# 2in-2out_1_0f_produziert_re.net
KiCad netlist of a schematic drawn in EAGLE
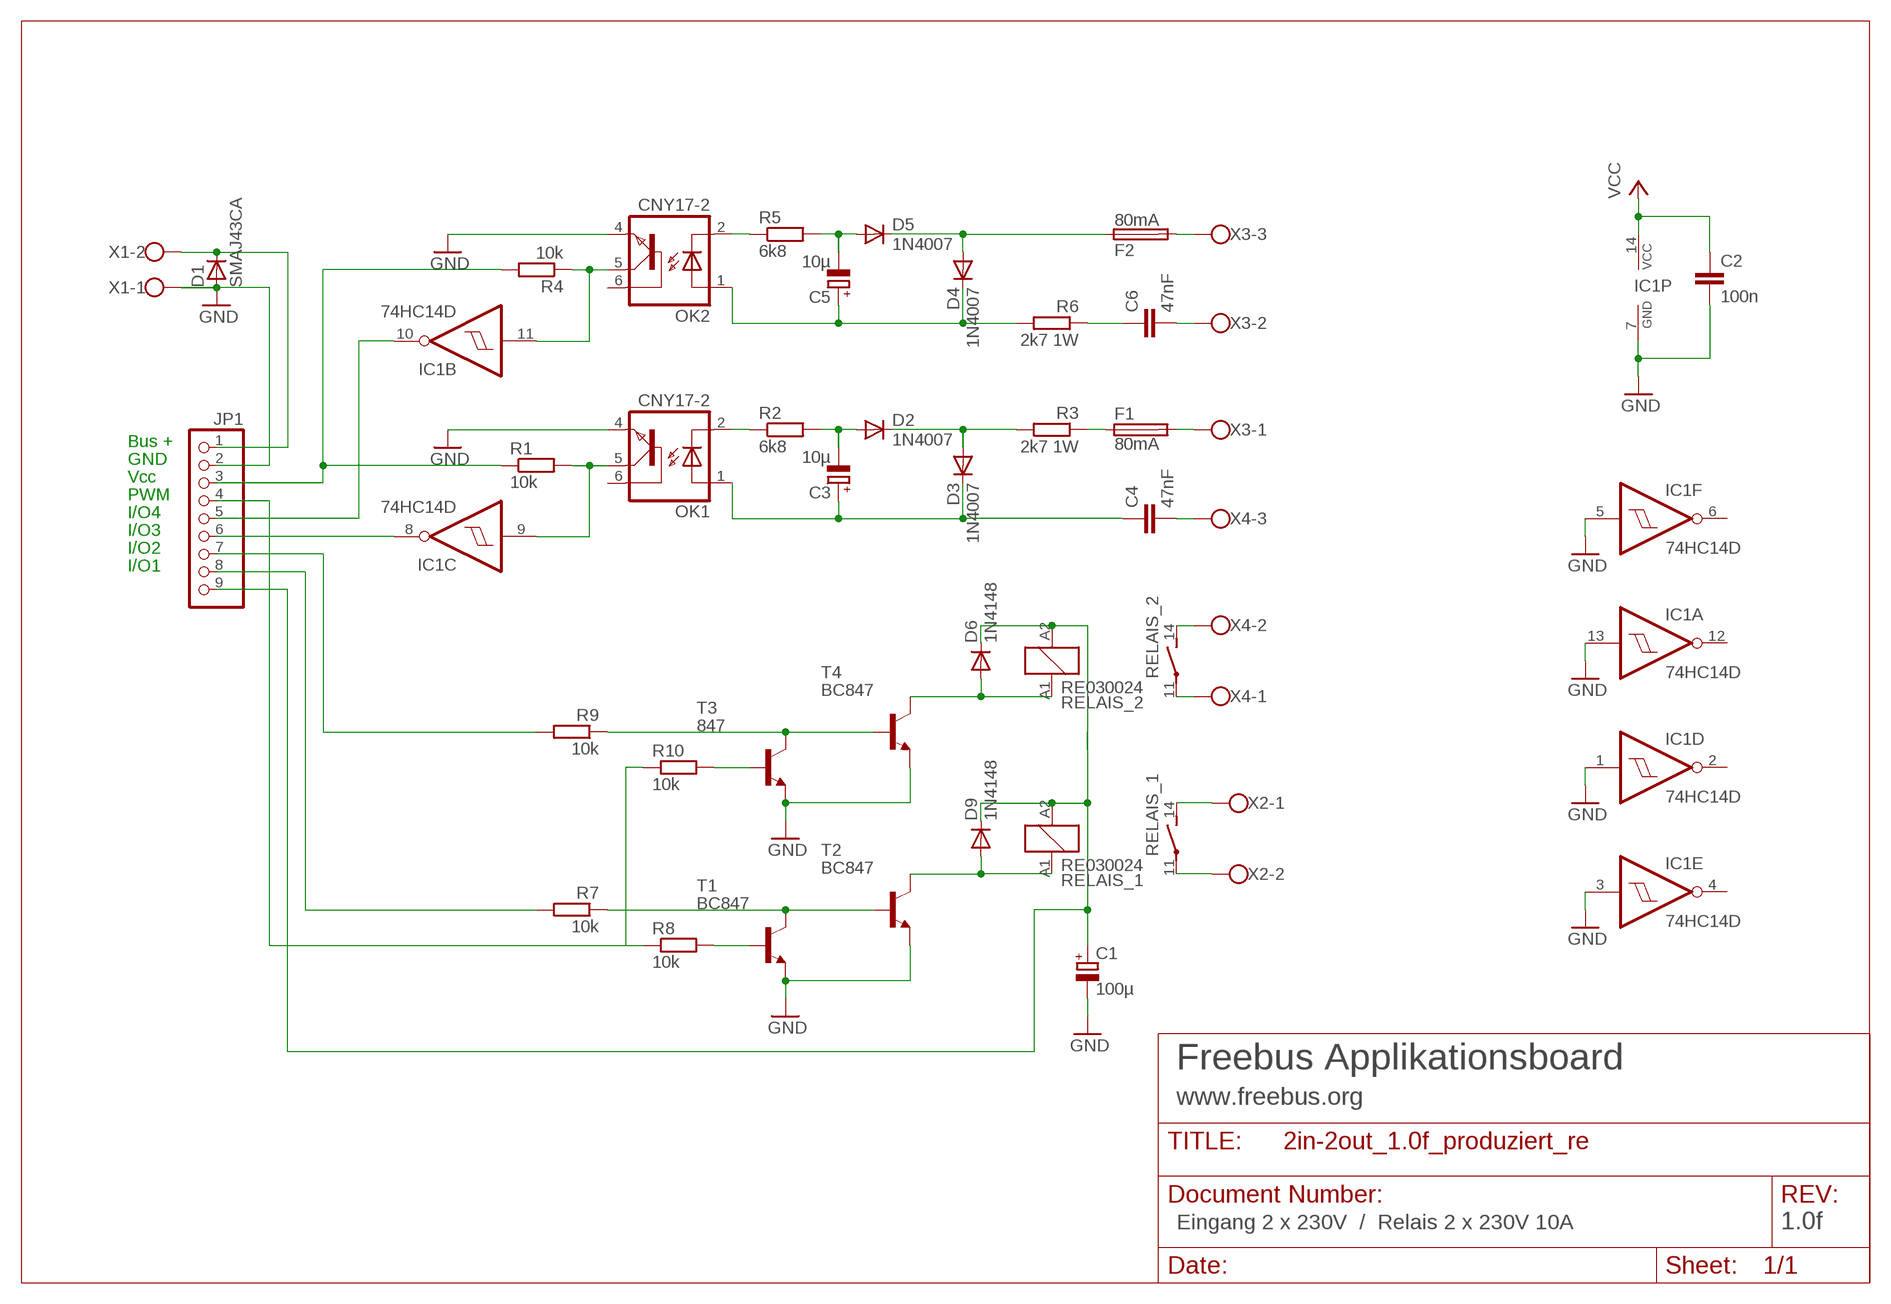
[diagram p0: schematic, sheet 1]

(export (version "E")
  (design (tool "Eeschema 10.0.6"))
  (components
    (comp (ref "C1")
      (value "100µ")
      (footprint "eagle-import:E3,5-8")
      (libsource (lib "eagle-import") (part "CPOL-EUE3.5-8"))
    )
    (comp (ref "C2")
      (value "100n")
      (footprint "eagle-import:C1206")
      (libsource (lib "eagle-import") (part "C-EUC1206"))
    )
    (comp (ref "C3")
      (value "10µ")
      (footprint "eagle-import:E2-4")
      (libsource (lib "eagle-import") (part "CPOL-EUE2-4"))
    )
    (comp (ref "C4")
      (value "47nF")
      (footprint "eagle-import:C075-063X106")
      (libsource (lib "eagle-import") (part "C-EU075-063X106"))
    )
    (comp (ref "C5")
      (value "10µ")
      (footprint "eagle-import:E2-4")
      (libsource (lib "eagle-import") (part "CPOL-EUE2-4"))
    )
    (comp (ref "C6")
      (value "47nF")
      (footprint "eagle-import:C075-063X106")
      (libsource (lib "eagle-import") (part "C-EU075-063X106"))
    )
    (comp (ref "D1")
      (value "SMAJ43CA")
      (footprint "eagle-import:SMB")
      (libsource (lib "eagle-import") (part "D-SMB"))
    )
    (comp (ref "D2")
      (value "1N4007")
      (footprint "eagle-import:D-2.5")
      (libsource (lib "eagle-import") (part "DIODE-D-2.5"))
    )
    (comp (ref "D3")
      (value "1N4007")
      (footprint "eagle-import:D-2.5")
      (libsource (lib "eagle-import") (part "DIODE-D-2.5"))
    )
    (comp (ref "D4")
      (value "1N4007")
      (footprint "eagle-import:D-2.5")
      (libsource (lib "eagle-import") (part "DIODE-D-2.5"))
    )
    (comp (ref "D5")
      (value "1N4007")
      (footprint "eagle-import:D-2.5")
      (libsource (lib "eagle-import") (part "DIODE-D-2.5"))
    )
    (comp (ref "D6")
      (value "1N4148")
      (footprint "eagle-import:MINIMELF")
      (libsource (lib "eagle-import") (part "DIODE-MINIMELF"))
    )
    (comp (ref "D9")
      (value "1N4148")
      (footprint "eagle-import:MINIMELF")
      (libsource (lib "eagle-import") (part "DIODE-MINIMELF"))
    )
    (comp (ref "F1")
      (value "80mA")
      (footprint "eagle-import:0617V")
      (libsource (lib "eagle-import") (part "FUSE"))
    )
    (comp (ref "F2")
      (value "80mA")
      (footprint "eagle-import:0617V")
      (libsource (lib "eagle-import") (part "FUSE"))
    )
    (comp (ref "IC1")
      (value "74HC14D")
      (footprint "eagle-import:SO14")
      (libsource (lib "eagle-import") (part "7414DHC"))
    )
    (comp (ref "JP1")
      (value "PINHD-1X9")
      (footprint "eagle-import:1X09")
      (libsource (lib "eagle-import") (part "PINHD-1X9"))
    )
    (comp (ref "OK1")
      (value "CNY17-2")
      (footprint "eagle-import:DIL06")
      (libsource (lib "eagle-import") (part "CNY17"))
    )
    (comp (ref "OK2")
      (value "CNY17-2")
      (footprint "eagle-import:DIL06")
      (libsource (lib "eagle-import") (part "CNY17"))
    )
    (comp (ref "R1")
      (value "10k")
      (footprint "eagle-import:M1206")
      (libsource (lib "eagle-import") (part "R-EU_M1206"))
    )
    (comp (ref "R2")
      (value "6k8")
      (footprint "eagle-import:0207_2V")
      (libsource (lib "eagle-import") (part "R-EU_0207/2V"))
    )
    (comp (ref "R3")
      (value "2k7 1W")
      (footprint "eagle-import:0207_2V")
      (libsource (lib "eagle-import") (part "R-EU_0207/2V"))
    )
    (comp (ref "R4")
      (value "10k")
      (footprint "eagle-import:M1206")
      (libsource (lib "eagle-import") (part "R-EU_M1206"))
    )
    (comp (ref "R5")
      (value "6k8")
      (footprint "eagle-import:0207_2V")
      (libsource (lib "eagle-import") (part "R-EU_0207/2V"))
    )
    (comp (ref "R6")
      (value "2k7 1W")
      (footprint "eagle-import:0207_2V")
      (libsource (lib "eagle-import") (part "R-EU_0207/2V"))
    )
    (comp (ref "R7")
      (value "10k")
      (footprint "eagle-import:M1206")
      (libsource (lib "eagle-import") (part "R-EU_M1206"))
    )
    (comp (ref "R8")
      (value "10k")
      (footprint "eagle-import:M1206")
      (libsource (lib "eagle-import") (part "R-EU_M1206"))
    )
    (comp (ref "R9")
      (value "10k")
      (footprint "eagle-import:M1206")
      (libsource (lib "eagle-import") (part "R-EU_M1206"))
    )
    (comp (ref "R10")
      (value "10k")
      (footprint "eagle-import:M1206")
      (libsource (lib "eagle-import") (part "R-EU_M1206"))
    )
    (comp (ref "RELAIS_1")
      (value "RE030024")
      (footprint "eagle-import:RE-SCHRACK")
      (libsource (lib "eagle-import") (part "RE030024"))
    )
    (comp (ref "RELAIS_2")
      (value "RE030024")
      (footprint "eagle-import:RE-SCHRACK")
      (libsource (lib "eagle-import") (part "RE030024"))
    )
    (comp (ref "T1")
      (value "BC847")
      (footprint "eagle-import:SOT23")
      (libsource (lib "eagle-import") (part "BC847"))
    )
    (comp (ref "T2")
      (value "BC847")
      (footprint "eagle-import:SOT23")
      (libsource (lib "eagle-import") (part "BC847"))
    )
    (comp (ref "T3")
      (value "847")
      (footprint "eagle-import:SOT23")
      (libsource (lib "eagle-import") (part "BC847"))
    )
    (comp (ref "T4")
      (value "BC847")
      (footprint "eagle-import:SOT23")
      (libsource (lib "eagle-import") (part "BC847"))
    )
    (comp (ref "X1")
      (value "W237-02P")
      (footprint "eagle-import:W237-132")
      (libsource (lib "eagle-import") (part "W237-02P"))
    )
    (comp (ref "X2")
      (value "W237-02P")
      (footprint "eagle-import:W237-132")
      (libsource (lib "eagle-import") (part "W237-02P"))
    )
    (comp (ref "X3")
      (value "W237-3E")
      (footprint "eagle-import:W237-3E")
      (libsource (lib "eagle-import") (part "W237-3E"))
    )
    (comp (ref "X4")
      (value "W237-3E")
      (footprint "eagle-import:W237-3E")
      (libsource (lib "eagle-import") (part "W237-3E"))
    )
  )
  (nets
    (net (code "1") (name "GND") (class "Default")
      (node (ref "C1") (pin "-") (pinfunction "-_-") (pintype "passive"))
      (node (ref "C2") (pin "2") (pinfunction "2_2") (pintype "passive"))
      (node (ref "D1") (pin "2") (pinfunction "A_2") (pintype "passive"))
      (node (ref "IC1") (pin "1") (pinfunction "I_1") (pintype "input"))
      (node (ref "IC1") (pin "13") (pinfunction "I_13") (pintype "input"))
      (node (ref "IC1") (pin "3") (pinfunction "I_3") (pintype "input"))
      (node (ref "IC1") (pin "5") (pinfunction "I_5") (pintype "input"))
      (node (ref "IC1") (pin "7") (pinfunction "GND_7") (pintype "power_in"))
      (node (ref "JP1") (pin "2") (pinfunction "2_2") (pintype "passive"))
      (node (ref "OK1") (pin "4") (pinfunction "EMI_4") (pintype "passive"))
      (node (ref "OK2") (pin "4") (pinfunction "EMI_4") (pintype "passive"))
      (node (ref "T1") (pin "2") (pinfunction "E_2") (pintype "passive"))
      (node (ref "T2") (pin "2") (pinfunction "E_2") (pintype "passive"))
      (node (ref "T3") (pin "2") (pinfunction "E_2") (pintype "passive"))
      (node (ref "T4") (pin "2") (pinfunction "E_2") (pintype "passive"))
      (node (ref "X1") (pin "1") (pinfunction "KL_1") (pintype "passive"))
    )
    (net (code "2") (name "Net-(C3-Pad-)") (class "Default")
      (node (ref "C3") (pin "-") (pinfunction "-_-") (pintype "passive"))
      (node (ref "D2") (pin "A") (pinfunction "A_A") (pintype "passive"))
      (node (ref "R2") (pin "2") (pinfunction "2_2") (pintype "passive"))
    )
    (net (code "3") (name "Net-(C5-Pad-)") (class "Default")
      (node (ref "C5") (pin "-") (pinfunction "-_-") (pintype "passive"))
      (node (ref "D5") (pin "A") (pinfunction "A_A") (pintype "passive"))
      (node (ref "R5") (pin "2") (pinfunction "2_2") (pintype "passive"))
    )
    (net (code "4") (name "Net-(C6-Pad1)") (class "Default")
      (node (ref "C6") (pin "1") (pinfunction "1_1") (pintype "passive"))
      (node (ref "R6") (pin "1") (pinfunction "1_1") (pintype "passive"))
    )
    (net (code "5") (name "Net-(D1-C)") (class "Default")
      (node (ref "D1") (pin "1") (pinfunction "C_1") (pintype "passive"))
      (node (ref "JP1") (pin "1") (pinfunction "1_1") (pintype "passive"))
      (node (ref "X1") (pin "2") (pinfunction "KL_2") (pintype "passive"))
    )
    (net (code "6") (name "Net-(D2-PadC)") (class "Default")
      (node (ref "D2") (pin "C") (pinfunction "C_C") (pintype "passive"))
      (node (ref "D3") (pin "A") (pinfunction "A_A") (pintype "passive"))
      (node (ref "R3") (pin "2") (pinfunction "2_2") (pintype "passive"))
    )
    (net (code "7") (name "Net-(D4-PadA)") (class "Default")
      (node (ref "D4") (pin "A") (pinfunction "A_A") (pintype "passive"))
      (node (ref "D5") (pin "C") (pinfunction "C_C") (pintype "passive"))
      (node (ref "F2") (pin "1") (pinfunction "1_1") (pintype "passive"))
    )
    (net (code "8") (name "Net-(F1-Pad1)") (class "Default")
      (node (ref "F1") (pin "1") (pinfunction "1_1") (pintype "passive"))
      (node (ref "R3") (pin "1") (pinfunction "1_1") (pintype "passive"))
    )
    (net (code "9") (name "Net-(IC1B-I)") (class "Default")
      (node (ref "IC1") (pin "11") (pinfunction "I_11") (pintype "input"))
      (node (ref "OK2") (pin "5") (pinfunction "COL_5") (pintype "passive"))
      (node (ref "R4") (pin "1") (pinfunction "1_1") (pintype "passive"))
    )
    (net (code "10") (name "Net-(IC1B-O)") (class "Default")
      (node (ref "IC1") (pin "10") (pinfunction "O_10") (pintype "output"))
      (node (ref "JP1") (pin "5") (pinfunction "5_5") (pintype "passive"))
    )
    (net (code "11") (name "Net-(IC1C-I)") (class "Default")
      (node (ref "IC1") (pin "9") (pinfunction "I_9") (pintype "input"))
      (node (ref "OK1") (pin "5") (pinfunction "COL_5") (pintype "passive"))
      (node (ref "R1") (pin "2") (pinfunction "2_2") (pintype "passive"))
    )
    (net (code "12") (name "Net-(IC1C-O)") (class "Default")
      (node (ref "IC1") (pin "8") (pinfunction "O_8") (pintype "output"))
      (node (ref "JP1") (pin "6") (pinfunction "6_6") (pintype "passive"))
    )
    (net (code "13") (name "Net-(JP1-Pad4)") (class "Default")
      (node (ref "JP1") (pin "4") (pinfunction "4_4") (pintype "passive"))
      (node (ref "R10") (pin "1") (pinfunction "1_1") (pintype "passive"))
      (node (ref "R8") (pin "1") (pinfunction "1_1") (pintype "passive"))
    )
    (net (code "14") (name "Net-(JP1-Pad7)") (class "Default")
      (node (ref "JP1") (pin "7") (pinfunction "7_7") (pintype "passive"))
      (node (ref "R9") (pin "2") (pinfunction "2_2") (pintype "passive"))
    )
    (net (code "15") (name "Net-(JP1-Pad8)") (class "Default")
      (node (ref "JP1") (pin "8") (pinfunction "8_8") (pintype "passive"))
      (node (ref "R7") (pin "2") (pinfunction "2_2") (pintype "passive"))
    )
    (net (code "16") (name "Net-(OK1-A)") (class "Default")
      (node (ref "C3") (pin "+") (pinfunction "+_+") (pintype "passive"))
      (node (ref "C4") (pin "1") (pinfunction "1_1") (pintype "passive"))
      (node (ref "D3") (pin "C") (pinfunction "C_C") (pintype "passive"))
      (node (ref "OK1") (pin "1") (pinfunction "A_1") (pintype "passive"))
    )
    (net (code "17") (name "Net-(OK1-C)") (class "Default")
      (node (ref "OK1") (pin "2") (pinfunction "C_2") (pintype "passive"))
      (node (ref "R2") (pin "1") (pinfunction "1_1") (pintype "passive"))
    )
    (net (code "18") (name "Net-(OK2-A)") (class "Default")
      (node (ref "C5") (pin "+") (pinfunction "+_+") (pintype "passive"))
      (node (ref "D4") (pin "C") (pinfunction "C_C") (pintype "passive"))
      (node (ref "OK2") (pin "1") (pinfunction "A_1") (pintype "passive"))
      (node (ref "R6") (pin "2") (pinfunction "2_2") (pintype "passive"))
    )
    (net (code "19") (name "Net-(OK2-C)") (class "Default")
      (node (ref "OK2") (pin "2") (pinfunction "C_2") (pintype "passive"))
      (node (ref "R5") (pin "1") (pinfunction "1_1") (pintype "passive"))
    )
    (net (code "20") (name "Net-(RELAIS_1A-1)") (class "Default")
      (node (ref "D9") (pin "A") (pinfunction "A_A") (pintype "passive"))
      (node (ref "RELAIS_1") (pin "A1") (pinfunction "1_A1") (pintype "passive"))
      (node (ref "T2") (pin "3") (pinfunction "C_3") (pintype "passive"))
    )
    (net (code "21") (name "Net-(RELAIS_1A-2)") (class "Default")
      (node (ref "C1") (pin "+") (pinfunction "+_+") (pintype "passive"))
      (node (ref "D6") (pin "C") (pinfunction "C_C") (pintype "passive"))
      (node (ref "D9") (pin "C") (pinfunction "C_C") (pintype "passive"))
      (node (ref "JP1") (pin "9") (pinfunction "9_9") (pintype "passive"))
      (node (ref "RELAIS_1") (pin "A2") (pinfunction "2_A2") (pintype "passive"))
      (node (ref "RELAIS_2") (pin "A2") (pinfunction "2_A2") (pintype "passive"))
    )
    (net (code "22") (name "Net-(RELAIS_1B-P)") (class "Default")
      (node (ref "RELAIS_1") (pin "11") (pinfunction "P_11") (pintype "passive"))
      (node (ref "X2") (pin "2") (pinfunction "KL_2") (pintype "passive"))
    )
    (net (code "23") (name "Net-(RELAIS_1B-S)") (class "Default")
      (node (ref "RELAIS_1") (pin "14") (pinfunction "S_14") (pintype "passive"))
      (node (ref "X2") (pin "1") (pinfunction "KL_1") (pintype "passive"))
    )
    (net (code "24") (name "Net-(RELAIS_2A-1)") (class "Default")
      (node (ref "D6") (pin "A") (pinfunction "A_A") (pintype "passive"))
      (node (ref "RELAIS_2") (pin "A1") (pinfunction "1_A1") (pintype "passive"))
      (node (ref "T4") (pin "3") (pinfunction "C_3") (pintype "passive"))
    )
    (net (code "25") (name "Net-(RELAIS_2B-P)") (class "Default")
      (node (ref "RELAIS_2") (pin "11") (pinfunction "P_11") (pintype "passive"))
      (node (ref "X4") (pin "1") (pinfunction "KL_1") (pintype "passive"))
    )
    (net (code "26") (name "Net-(RELAIS_2B-S)") (class "Default")
      (node (ref "RELAIS_2") (pin "14") (pinfunction "S_14") (pintype "passive"))
      (node (ref "X4") (pin "2") (pinfunction "KL_2") (pintype "passive"))
    )
    (net (code "27") (name "Net-(T1-B)") (class "Default")
      (node (ref "R8") (pin "2") (pinfunction "2_2") (pintype "passive"))
      (node (ref "T1") (pin "1") (pinfunction "B_1") (pintype "passive"))
    )
    (net (code "28") (name "Net-(T1-C)") (class "Default")
      (node (ref "R7") (pin "1") (pinfunction "1_1") (pintype "passive"))
      (node (ref "T1") (pin "3") (pinfunction "C_3") (pintype "passive"))
      (node (ref "T2") (pin "1") (pinfunction "B_1") (pintype "passive"))
    )
    (net (code "29") (name "Net-(T3-B)") (class "Default")
      (node (ref "R10") (pin "2") (pinfunction "2_2") (pintype "passive"))
      (node (ref "T3") (pin "1") (pinfunction "B_1") (pintype "passive"))
    )
    (net (code "30") (name "Net-(T3-C)") (class "Default")
      (node (ref "R9") (pin "1") (pinfunction "1_1") (pintype "passive"))
      (node (ref "T3") (pin "3") (pinfunction "C_3") (pintype "passive"))
      (node (ref "T4") (pin "1") (pinfunction "B_1") (pintype "passive"))
    )
    (net (code "31") (name "Net-(X3A-KL)") (class "Default")
      (node (ref "F1") (pin "2") (pinfunction "2_2") (pintype "passive"))
      (node (ref "X3") (pin "1") (pinfunction "KL_1") (pintype "passive"))
    )
    (net (code "32") (name "Net-(X3B-KL)") (class "Default")
      (node (ref "C6") (pin "2") (pinfunction "2_2") (pintype "passive"))
      (node (ref "X3") (pin "2") (pinfunction "KL_2") (pintype "passive"))
    )
    (net (code "33") (name "Net-(X3C-KL)") (class "Default")
      (node (ref "F2") (pin "2") (pinfunction "2_2") (pintype "passive"))
      (node (ref "X3") (pin "3") (pinfunction "KL_3") (pintype "passive"))
    )
    (net (code "34") (name "Net-(X4C-KL)") (class "Default")
      (node (ref "C4") (pin "2") (pinfunction "2_2") (pintype "passive"))
      (node (ref "X4") (pin "3") (pinfunction "KL_3") (pintype "passive"))
    )
    (net (code "35") (name "VCC") (class "Default")
      (node (ref "C2") (pin "1") (pinfunction "1_1") (pintype "passive"))
      (node (ref "IC1") (pin "14") (pinfunction "VCC_14") (pintype "power_in"))
      (node (ref "JP1") (pin "3") (pinfunction "3_3") (pintype "passive"))
      (node (ref "R1") (pin "1") (pinfunction "1_1") (pintype "passive"))
      (node (ref "R4") (pin "2") (pinfunction "2_2") (pintype "passive"))
    )
    (net (code "36") (name "unconnected-(IC1A-O-Pad12)") (class "Default")
      (node (ref "IC1") (pin "12") (pinfunction "O_12") (pintype "output"))
    )
    (net (code "37") (name "unconnected-(IC1D-O-Pad2)") (class "Default")
      (node (ref "IC1") (pin "2") (pinfunction "O_2") (pintype "output"))
    )
    (net (code "38") (name "unconnected-(IC1E-O-Pad4)") (class "Default")
      (node (ref "IC1") (pin "4") (pinfunction "O_4") (pintype "output"))
    )
    (net (code "39") (name "unconnected-(IC1F-O-Pad6)") (class "Default")
      (node (ref "IC1") (pin "6") (pinfunction "O_6") (pintype "output"))
    )
    (net (code "40") (name "unconnected-(OK1-BAS-Pad6)") (class "Default")
      (node (ref "OK1") (pin "6") (pinfunction "BAS_6") (pintype "passive"))
    )
    (net (code "41") (name "unconnected-(OK2-BAS-Pad6)") (class "Default")
      (node (ref "OK2") (pin "6") (pinfunction "BAS_6") (pintype "passive"))
    )
  )
)
